# Power.net
KiCad netlist of a schematic drawn in Altium Designer
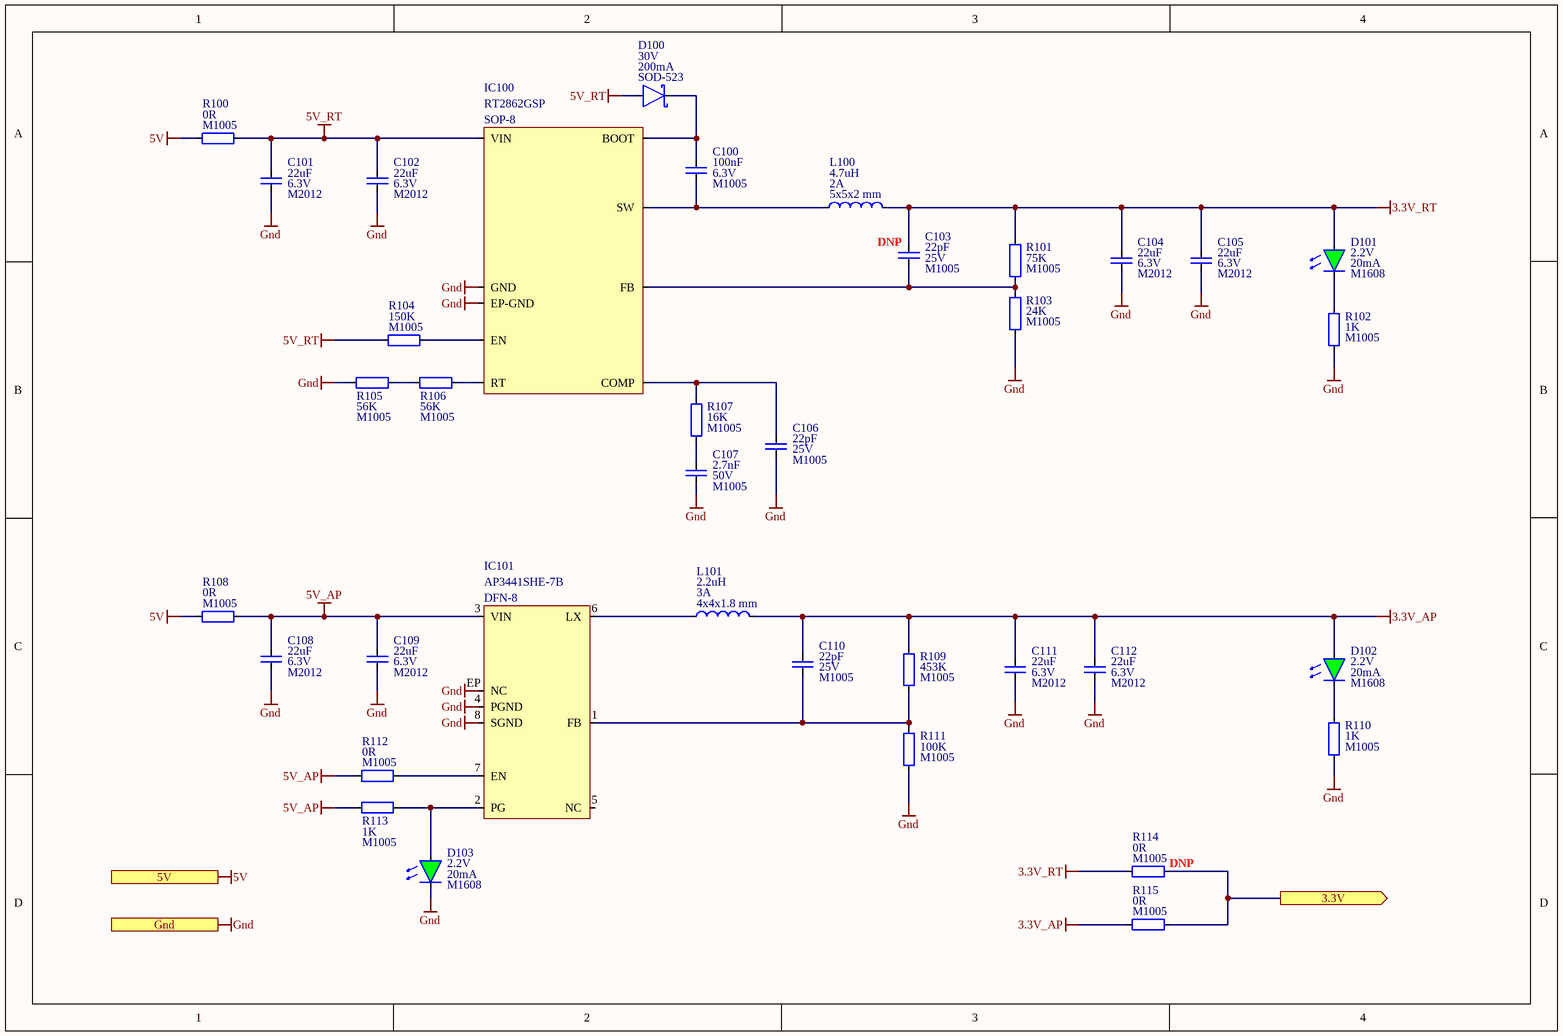
[diagram p0: Power.SchDoc]

(export (version "E")
  (design (tool "Eeschema 10.0.6"))
  (components
    (comp (ref "C100")
      (value "100nF")
      (footprint "Capacitor_Ceramic_M1005_I0402")
      (description "Cap, Cer, 100nF, 6.3V, M1005")
      (fields
        (field (name "VOLTAGE") "6.3V")
        (field (name "MANUFACTURER PART NUMBER") "04026D104KAT4A")
        (field (name "MANUFACTURER") "Kyocera")
        (field (name "PACKAGE") "M1005")
      )
      (libsource (lib "Capacitor") (part "Capacitor_Ceramic"))
    )
    (comp (ref "C101")
      (value "22uF")
      (footprint "Capacitor_Ceramic_M2012_I0805")
      (description "Cap, Cer, 22uF, 6.3V, M2012")
      (fields
        (field (name "VOLTAGE") "6.3V")
        (field (name "MANUFACTURER PART NUMBER") "GRM21BR60J226ME39K")
        (field (name "MANUFACTURER") "Murata")
        (field (name "PACKAGE") "M2012")
      )
      (libsource (lib "Capacitor") (part "Capacitor_Ceramic"))
    )
    (comp (ref "C102")
      (value "22uF")
      (footprint "Capacitor_Ceramic_M2012_I0805")
      (description "Cap, Cer, 22uF, 6.3V, M2012")
      (fields
        (field (name "VOLTAGE") "6.3V")
        (field (name "MANUFACTURER PART NUMBER") "GRM21BR60J226ME39K")
        (field (name "MANUFACTURER") "Murata")
        (field (name "PACKAGE") "M2012")
      )
      (libsource (lib "Capacitor") (part "Capacitor_Ceramic"))
    )
    (comp (ref "C103")
      (value "22pF")
      (footprint "Capacitor_Ceramic_M1005_I0402")
      (description "Cap, Cer, 22pF, 25V, M1005")
      (fields
        (field (name "VOLTAGE") "25V")
        (field (name "MANUFACTURER PART NUMBER") "0402N220J250CT")
        (field (name "MANUFACTURER") "Walsin")
        (field (name "PACKAGE") "M1005")
      )
      (libsource (lib "Capacitor") (part "Capacitor_Ceramic"))
    )
    (comp (ref "C104")
      (value "22uF")
      (footprint "Capacitor_Ceramic_M2012_I0805")
      (description "Cap, Cer, 22uF, 6.3V, M2012")
      (fields
        (field (name "VOLTAGE") "6.3V")
        (field (name "MANUFACTURER PART NUMBER") "GRM21BR60J226ME39K")
        (field (name "MANUFACTURER") "Murata")
        (field (name "PACKAGE") "M2012")
      )
      (libsource (lib "Capacitor") (part "Capacitor_Ceramic"))
    )
    (comp (ref "C105")
      (value "22uF")
      (footprint "Capacitor_Ceramic_M2012_I0805")
      (description "Cap, Cer, 22uF, 6.3V, M2012")
      (fields
        (field (name "VOLTAGE") "6.3V")
        (field (name "MANUFACTURER PART NUMBER") "GRM21BR60J226ME39K")
        (field (name "MANUFACTURER") "Murata")
        (field (name "PACKAGE") "M2012")
      )
      (libsource (lib "Capacitor") (part "Capacitor_Ceramic"))
    )
    (comp (ref "C106")
      (value "22pF")
      (footprint "Capacitor_Ceramic_M1005_I0402")
      (description "Cap, Cer, 22pF, 25V, M1005")
      (fields
        (field (name "VOLTAGE") "25V")
        (field (name "MANUFACTURER PART NUMBER") "0402N220J250CT")
        (field (name "MANUFACTURER") "Walsin")
        (field (name "PACKAGE") "M1005")
      )
      (libsource (lib "Capacitor") (part "Capacitor_Ceramic"))
    )
    (comp (ref "C107")
      (value "2.7nF")
      (footprint "Capacitor_Ceramic_M1005_I0402")
      (description "Cap, Cer, 2.7nF, 50V, M1005")
      (fields
        (field (name "VOLTAGE") "50V")
        (field (name "MANUFACTURER PART NUMBER") "CC0402KRX7R9BB272")
        (field (name "MANUFACTURER") "Walsin")
        (field (name "PACKAGE") "M1005")
      )
      (libsource (lib "Capacitor") (part "Capacitor_Ceramic"))
    )
    (comp (ref "C108")
      (value "22uF")
      (footprint "Capacitor_Ceramic_M2012_I0805")
      (description "Cap, Cer, 22uF, 6.3V, M2012")
      (fields
        (field (name "VOLTAGE") "6.3V")
        (field (name "MANUFACTURER PART NUMBER") "GRM21BR60J226ME39K")
        (field (name "MANUFACTURER") "Murata")
        (field (name "PACKAGE") "M2012")
      )
      (libsource (lib "Capacitor") (part "Capacitor_Ceramic"))
    )
    (comp (ref "C109")
      (value "22uF")
      (footprint "Capacitor_Ceramic_M2012_I0805")
      (description "Cap, Cer, 22uF, 6.3V, M2012")
      (fields
        (field (name "VOLTAGE") "6.3V")
        (field (name "MANUFACTURER PART NUMBER") "GRM21BR60J226ME39K")
        (field (name "MANUFACTURER") "Murata")
        (field (name "PACKAGE") "M2012")
      )
      (libsource (lib "Capacitor") (part "Capacitor_Ceramic"))
    )
    (comp (ref "C110")
      (value "22pF")
      (footprint "Capacitor_Ceramic_M1005_I0402")
      (description "Cap, Cer, 22pF, 25V, M1005")
      (fields
        (field (name "VOLTAGE") "25V")
        (field (name "MANUFACTURER PART NUMBER") "0402N220J250CT")
        (field (name "MANUFACTURER") "Walsin")
        (field (name "PACKAGE") "M1005")
      )
      (libsource (lib "Capacitor") (part "Capacitor_Ceramic"))
    )
    (comp (ref "C111")
      (value "22uF")
      (footprint "Capacitor_Ceramic_M2012_I0805")
      (description "Cap, Cer, 22uF, 6.3V, M2012")
      (fields
        (field (name "VOLTAGE") "6.3V")
        (field (name "MANUFACTURER PART NUMBER") "GRM21BR60J226ME39K")
        (field (name "MANUFACTURER") "Murata")
        (field (name "PACKAGE") "M2012")
      )
      (libsource (lib "Capacitor") (part "Capacitor_Ceramic"))
    )
    (comp (ref "C112")
      (value "22uF")
      (footprint "Capacitor_Ceramic_M2012_I0805")
      (description "Cap, Cer, 22uF, 6.3V, M2012")
      (fields
        (field (name "VOLTAGE") "6.3V")
        (field (name "MANUFACTURER PART NUMBER") "GRM21BR60J226ME39K")
        (field (name "MANUFACTURER") "Murata")
        (field (name "PACKAGE") "M2012")
      )
      (libsource (lib "Capacitor") (part "Capacitor_Ceramic"))
    )
    (comp (ref "D100")
      (value "Diode_Schottky")
      (footprint "Diode_SOD-523_SC-79")
      (description "Diode, Schottky, 30V, 200mA, SOD-523")
      (fields
        (field (name "MANUFACTURER PART NUMBER") "CES521,L3F")
        (field (name "MANUFACTURER") "Toshiba")
        (field (name "CURRENT") "200mA")
        (field (name "VOLTAGE") "30V")
        (field (name "PACKAGE") "SOD-523")
      )
      (libsource (lib "Diode") (part "Diode_Schottky"))
    )
    (comp (ref "D101")
      (value "Diode_Led")
      (footprint "Diode_Smd_M1608_I0603_Green-Yellow")
      (description "Diode, Led, Green-Yellow, 2.2V, 20mA, M1608")
      (fields
        (field (name "MANUFACTURER PART NUMBER") "SML-D12M1WT86")
        (field (name "MANUFACTURER") "Rohm")
        (field (name "CURRENT") "20mA")
        (field (name "VOLTAGE") "2.2V")
        (field (name "PACKAGE") "M1608")
      )
      (libsource (lib "Diode") (part "Diode_Led"))
    )
    (comp (ref "D102")
      (value "Diode_Led")
      (footprint "Diode_Smd_M1608_I0603_Green-Yellow")
      (description "Diode, Led, Green-Yellow, 2.2V, 20mA, M1608")
      (fields
        (field (name "MANUFACTURER PART NUMBER") "SML-D12M1WT86")
        (field (name "MANUFACTURER") "Rohm")
        (field (name "CURRENT") "20mA")
        (field (name "VOLTAGE") "2.2V")
        (field (name "PACKAGE") "M1608")
      )
      (libsource (lib "Diode") (part "Diode_Led"))
    )
    (comp (ref "D103")
      (value "Diode_Led")
      (footprint "Diode_Smd_M1608_I0603_Green-Yellow")
      (description "Diode, Led, Green-Yellow, 2.2V, 20mA, M1608")
      (fields
        (field (name "MANUFACTURER PART NUMBER") "SML-D12M1WT86")
        (field (name "MANUFACTURER") "Rohm")
        (field (name "CURRENT") "20mA")
        (field (name "VOLTAGE") "2.2V")
        (field (name "PACKAGE") "M1608")
      )
      (libsource (lib "Diode") (part "Diode_Led"))
    )
    (comp (ref "IC100")
      (value "Richtek, RT2862xSP")
      (footprint "Richtek, RT2862xSP, SOP-8")
      (description "IC, Power, Buck, SOP-8")
      (fields
        (field (name "MANUFACTURER") "Richtek")
        (field (name "MANUFACTURER PART NUMBER") "RT2862GSP")
        (field (name "PACKAGE") "SOP-8")
      )
      (libsource (lib "IC - Power - DC-DC") (part "Richtek, RT2862xSP"))
    )
    (comp (ref "IC101")
      (value "Diodes, AP3441")
      (footprint "DFN-8, 2mm x 2mm, 0.5mm")
      (description "IC, Power, Buck, DFN-8, 2x2")
      (fields
        (field (name "MANUFACTURER") "Richtek")
        (field (name "MANUFACTURER PART NUMBER") "AP3441SHE-7B")
        (field (name "PACKAGE") "DFN-8")
      )
      (libsource (lib "IC - Power - DC-DC") (part "Diodes, AP3441"))
    )
    (comp (ref "L100")
      (value "4.7uH")
      (footprint "Taiyo Yuden - Power Inductor, 5050WK")
      (description "Inductor, Power, 4.7uH, 2A, 5x5x2mm")
      (fields
        (field (name "MANUFACTURER PART NUMBER") "NRS5020T4R7MMGJ")
        (field (name "MANUFACTURER") "Taiyo Yuden")
        (field (name "SATURATION CURRENT") "2A")
        (field (name "PACKAGE") "5x5x2 mm")
      )
      (libsource (lib "Inductor") (part "Inductor"))
    )
    (comp (ref "L101")
      (value "2.2uH")
      (footprint "Taiyo Yuden - Power Inductor, 4040TK")
      (description "Inductor, Power, 2.2uH, 3A, 4x4x1.8mm")
      (fields
        (field (name "MANUFACTURER PART NUMBER") "NRS4018T2R2MDGJ")
        (field (name "MANUFACTURER") "Taiyo Yuden")
        (field (name "SATURATION CURRENT") "3A")
        (field (name "PACKAGE") "4x4x1.8 mm")
      )
      (libsource (lib "Inductor") (part "Inductor"))
    )
    (comp (ref "R100")
      (value "0R")
      (footprint "Resistor_Smd_M1005_I0402")
      (description "Res, 0R, M1005")
      (fields
        (field (name "MANUFACTURER") "Yageo")
        (field (name "MANUFACTURER PART NUMBER") "RC0402FR-070RL")
        (field (name "PACKAGE") "M1005")
      )
      (libsource (lib "Resistor") (part "Resistor"))
    )
    (comp (ref "R101")
      (value "75K")
      (footprint "Resistor_Smd_M1005_I0402")
      (description "Res, 75K, 1%, M1005")
      (fields
        (field (name "TOLERANCE") "1%")
        (field (name "MANUFACTURER") "Yageo")
        (field (name "PACKAGE") "M1005")
      )
      (libsource (lib "Resistor") (part "Resistor"))
    )
    (comp (ref "R102")
      (value "1K")
      (footprint "Resistor_Smd_M1005_I0402")
      (description "Res, 1K, 1%, M1005")
      (fields
        (field (name "TOLERANCE") "1%")
        (field (name "MANUFACTURER") "Yageo")
        (field (name "PACKAGE") "M1005")
      )
      (libsource (lib "Resistor") (part "Resistor"))
    )
    (comp (ref "R103")
      (value "24K")
      (footprint "Resistor_Smd_M1005_I0402")
      (description "Res, 24K, 1%, M1005")
      (fields
        (field (name "TOLERANCE") "1%")
        (field (name "MANUFACTURER") "Yageo")
        (field (name "PACKAGE") "M1005")
      )
      (libsource (lib "Resistor") (part "Resistor"))
    )
    (comp (ref "R104")
      (value "150K")
      (footprint "Resistor_Smd_M1005_I0402")
      (description "Res, 150K, 1%, M1005")
      (fields
        (field (name "TOLERANCE") "1%")
        (field (name "MANUFACTURER") "Yageo")
        (field (name "PACKAGE") "M1005")
      )
      (libsource (lib "Resistor") (part "Resistor"))
    )
    (comp (ref "R105")
      (value "56K")
      (footprint "Resistor_Smd_M1005_I0402")
      (description "Res, 56K, 1%, M1005")
      (fields
        (field (name "TOLERANCE") "1%")
        (field (name "MANUFACTURER") "Yageo")
        (field (name "PACKAGE") "M1005")
      )
      (libsource (lib "Resistor") (part "Resistor"))
    )
    (comp (ref "R106")
      (value "56K")
      (footprint "Resistor_Smd_M1005_I0402")
      (description "Res, 56K, 1%, M1005")
      (fields
        (field (name "TOLERANCE") "1%")
        (field (name "MANUFACTURER") "Yageo")
        (field (name "PACKAGE") "M1005")
      )
      (libsource (lib "Resistor") (part "Resistor"))
    )
    (comp (ref "R107")
      (value "16K")
      (footprint "Resistor_Smd_M1005_I0402")
      (description "Res, 16K, 1%, M1005")
      (fields
        (field (name "TOLERANCE") "1%")
        (field (name "MANUFACTURER") "Yageo")
        (field (name "PACKAGE") "M1005")
      )
      (libsource (lib "Resistor") (part "Resistor"))
    )
    (comp (ref "R108")
      (value "0R")
      (footprint "Resistor_Smd_M1005_I0402")
      (description "Res, 0R, M1005")
      (fields
        (field (name "MANUFACTURER") "Yageo")
        (field (name "MANUFACTURER PART NUMBER") "RC0402FR-070RL")
        (field (name "PACKAGE") "M1005")
      )
      (libsource (lib "Resistor") (part "Resistor"))
    )
    (comp (ref "R109")
      (value "453K")
      (footprint "Resistor_Smd_M1005_I0402")
      (description "Res, 453K, 1%, M1005")
      (fields
        (field (name "TOLERANCE") "1%")
        (field (name "MANUFACTURER") "Yageo")
        (field (name "PACKAGE") "M1005")
      )
      (libsource (lib "Resistor") (part "Resistor"))
    )
    (comp (ref "R110")
      (value "1K")
      (footprint "Resistor_Smd_M1005_I0402")
      (description "Res, 1K, 1%, M1005")
      (fields
        (field (name "TOLERANCE") "1%")
        (field (name "MANUFACTURER") "Yageo")
        (field (name "PACKAGE") "M1005")
      )
      (libsource (lib "Resistor") (part "Resistor"))
    )
    (comp (ref "R111")
      (value "100K")
      (footprint "Resistor_Smd_M1005_I0402")
      (description "Res, 100K, 1%, M1005")
      (fields
        (field (name "TOLERANCE") "1%")
        (field (name "MANUFACTURER") "Yageo")
        (field (name "PACKAGE") "M1005")
      )
      (libsource (lib "Resistor") (part "Resistor"))
    )
    (comp (ref "R112")
      (value "0R")
      (footprint "Resistor_Smd_M1005_I0402")
      (description "Res, 0R, M1005")
      (fields
        (field (name "MANUFACTURER") "Yageo")
        (field (name "MANUFACTURER PART NUMBER") "RC0402FR-070RL")
        (field (name "PACKAGE") "M1005")
      )
      (libsource (lib "Resistor") (part "Resistor"))
    )
    (comp (ref "R113")
      (value "1K")
      (footprint "Resistor_Smd_M1005_I0402")
      (description "Res, 1K, 1%, M1005")
      (fields
        (field (name "TOLERANCE") "1%")
        (field (name "MANUFACTURER") "Yageo")
        (field (name "PACKAGE") "M1005")
      )
      (libsource (lib "Resistor") (part "Resistor"))
    )
    (comp (ref "R114")
      (value "0R")
      (footprint "Resistor_Smd_M1005_I0402")
      (description "Res, 0R, M1005")
      (fields
        (field (name "MANUFACTURER") "Yageo")
        (field (name "MANUFACTURER PART NUMBER") "RC0402FR-070RL")
        (field (name "PACKAGE") "M1005")
      )
      (libsource (lib "Resistor") (part "Resistor"))
    )
    (comp (ref "R115")
      (value "0R")
      (footprint "Resistor_Smd_M1005_I0402")
      (description "Res, 0R, M1005")
      (fields
        (field (name "MANUFACTURER") "Yageo")
        (field (name "MANUFACTURER PART NUMBER") "RC0402FR-070RL")
        (field (name "PACKAGE") "M1005")
      )
      (libsource (lib "Resistor") (part "Resistor"))
    )
  )
  (nets
    (net (code "1") (name "/3.3V") (class "Default")
      (node (ref "R114") (pin "2") (pinfunction "2_2") (pintype "passive"))
      (node (ref "R115") (pin "2") (pinfunction "2_2") (pintype "passive"))
    )
    (net (code "2") (name "3.3V_AP") (class "Default")
      (node (ref "C110") (pin "1") (pinfunction "1_1") (pintype "passive"))
      (node (ref "C111") (pin "1") (pinfunction "1_1") (pintype "passive"))
      (node (ref "C112") (pin "1") (pinfunction "1_1") (pintype "passive"))
      (node (ref "D102") (pin "A") (pinfunction "A_A") (pintype "passive"))
      (node (ref "L101") (pin "2") (pinfunction "2_2") (pintype "passive"))
      (node (ref "R109") (pin "1") (pinfunction "1_1") (pintype "passive"))
      (node (ref "R115") (pin "1") (pinfunction "1_1") (pintype "passive"))
    )
    (net (code "3") (name "3.3V_RT") (class "Default")
      (node (ref "C103") (pin "1") (pinfunction "1_1") (pintype "passive"))
      (node (ref "C104") (pin "1") (pinfunction "1_1") (pintype "passive"))
      (node (ref "C105") (pin "1") (pinfunction "1_1") (pintype "passive"))
      (node (ref "D101") (pin "A") (pinfunction "A_A") (pintype "passive"))
      (node (ref "L100") (pin "2") (pinfunction "2_2") (pintype "passive"))
      (node (ref "R101") (pin "1") (pinfunction "1_1") (pintype "passive"))
      (node (ref "R114") (pin "1") (pinfunction "1_1") (pintype "passive"))
    )
    (net (code "4") (name "5V") (class "Default")
      (node (ref "R100") (pin "1") (pinfunction "1_1") (pintype "passive"))
      (node (ref "R108") (pin "1") (pinfunction "1_1") (pintype "passive"))
    )
    (net (code "5") (name "5V_AP") (class "Default")
      (node (ref "C108") (pin "1") (pinfunction "1_1") (pintype "passive"))
      (node (ref "C109") (pin "1") (pinfunction "1_1") (pintype "passive"))
      (node (ref "IC101") (pin "3") (pinfunction "VIN_3") (pintype "passive"))
      (node (ref "R108") (pin "2") (pinfunction "2_2") (pintype "passive"))
      (node (ref "R112") (pin "1") (pinfunction "1_1") (pintype "passive"))
      (node (ref "R113") (pin "1") (pinfunction "1_1") (pintype "passive"))
    )
    (net (code "6") (name "5V_RT") (class "Default")
      (node (ref "C101") (pin "1") (pinfunction "1_1") (pintype "passive"))
      (node (ref "C102") (pin "1") (pinfunction "1_1") (pintype "passive"))
      (node (ref "D100") (pin "A") (pinfunction "A_A") (pintype "passive"))
      (node (ref "IC100") (pin "8-VIN") (pinfunction "VIN_8-VIN") (pintype "passive"))
      (node (ref "R100") (pin "2") (pinfunction "2_2") (pintype "passive"))
      (node (ref "R104") (pin "1") (pinfunction "1_1") (pintype "passive"))
    )
    (net (code "7") (name "Gnd") (class "Default")
      (node (ref "C101") (pin "2") (pinfunction "2_2") (pintype "passive"))
      (node (ref "C102") (pin "2") (pinfunction "2_2") (pintype "passive"))
      (node (ref "C104") (pin "2") (pinfunction "2_2") (pintype "passive"))
      (node (ref "C105") (pin "2") (pinfunction "2_2") (pintype "passive"))
      (node (ref "C106") (pin "2") (pinfunction "2_2") (pintype "passive"))
      (node (ref "C107") (pin "2") (pinfunction "2_2") (pintype "passive"))
      (node (ref "C108") (pin "2") (pinfunction "2_2") (pintype "passive"))
      (node (ref "C109") (pin "2") (pinfunction "2_2") (pintype "passive"))
      (node (ref "C111") (pin "2") (pinfunction "2_2") (pintype "passive"))
      (node (ref "C112") (pin "2") (pinfunction "2_2") (pintype "passive"))
      (node (ref "D103") (pin "C") (pinfunction "C_C") (pintype "passive"))
      (node (ref "IC100") (pin "4-GND") (pinfunction "GND_4-GND") (pintype "passive"))
      (node (ref "IC100") (pin "EP-GND") (pinfunction "EP-GND_EP-GND") (pintype "passive"))
      (node (ref "IC101") (pin "4") (pinfunction "PGND_4") (pintype "passive"))
      (node (ref "IC101") (pin "8") (pinfunction "SGND_8") (pintype "passive"))
      (node (ref "IC101") (pin "EP") (pinfunction "NC_EP") (pintype "passive"))
      (node (ref "R102") (pin "2") (pinfunction "2_2") (pintype "passive"))
      (node (ref "R103") (pin "2") (pinfunction "2_2") (pintype "passive"))
      (node (ref "R105") (pin "1") (pinfunction "1_1") (pintype "passive"))
      (node (ref "R110") (pin "2") (pinfunction "2_2") (pintype "passive"))
      (node (ref "R111") (pin "2") (pinfunction "2_2") (pintype "passive"))
    )
    (net (code "8") (name "Net-(C107-Pad1)") (class "Default")
      (node (ref "C107") (pin "1") (pinfunction "1_1") (pintype "passive"))
      (node (ref "R107") (pin "2") (pinfunction "2_2") (pintype "passive"))
    )
    (net (code "9") (name "Net-(D101-PadC)") (class "Default")
      (node (ref "D101") (pin "C") (pinfunction "C_C") (pintype "passive"))
      (node (ref "R102") (pin "1") (pinfunction "1_1") (pintype "passive"))
    )
    (net (code "10") (name "Net-(D102-PadC)") (class "Default")
      (node (ref "D102") (pin "C") (pinfunction "C_C") (pintype "passive"))
      (node (ref "R110") (pin "1") (pinfunction "1_1") (pintype "passive"))
    )
    (net (code "11") (name "Net-(IC100-BOOT)") (class "Default")
      (node (ref "C100") (pin "1") (pinfunction "1_1") (pintype "passive"))
      (node (ref "D100") (pin "C") (pinfunction "C_C") (pintype "passive"))
      (node (ref "IC100") (pin "2-BOOT") (pinfunction "BOOT_2-BOOT") (pintype "passive"))
    )
    (net (code "12") (name "Net-(IC100-COMP)") (class "Default")
      (node (ref "C106") (pin "1") (pinfunction "1_1") (pintype "passive"))
      (node (ref "IC100") (pin "6-COMP") (pinfunction "COMP_6-COMP") (pintype "passive"))
      (node (ref "R107") (pin "1") (pinfunction "1_1") (pintype "passive"))
    )
    (net (code "13") (name "Net-(IC100-EN)") (class "Default")
      (node (ref "IC100") (pin "3-EN") (pinfunction "EN_3-EN") (pintype "passive"))
      (node (ref "R104") (pin "2") (pinfunction "2_2") (pintype "passive"))
    )
    (net (code "14") (name "Net-(IC100-FB)") (class "Default")
      (node (ref "C103") (pin "2") (pinfunction "2_2") (pintype "passive"))
      (node (ref "IC100") (pin "5-FB") (pinfunction "FB_5-FB") (pintype "passive"))
      (node (ref "R101") (pin "2") (pinfunction "2_2") (pintype "passive"))
      (node (ref "R103") (pin "1") (pinfunction "1_1") (pintype "passive"))
    )
    (net (code "15") (name "Net-(IC100-RT)") (class "Default")
      (node (ref "IC100") (pin "7-RT") (pinfunction "RT_7-RT") (pintype "passive"))
      (node (ref "R106") (pin "2") (pinfunction "2_2") (pintype "passive"))
    )
    (net (code "16") (name "Net-(IC100-SW)") (class "Default")
      (node (ref "C100") (pin "2") (pinfunction "2_2") (pintype "passive"))
      (node (ref "IC100") (pin "1-SW") (pinfunction "SW_1-SW") (pintype "passive"))
      (node (ref "L100") (pin "1") (pinfunction "1_1") (pintype "passive"))
    )
    (net (code "17") (name "Net-(IC101-EN)") (class "Default")
      (node (ref "IC101") (pin "7") (pinfunction "EN_7") (pintype "passive"))
      (node (ref "R112") (pin "2") (pinfunction "2_2") (pintype "passive"))
    )
    (net (code "18") (name "Net-(IC101-FB)") (class "Default")
      (node (ref "C110") (pin "2") (pinfunction "2_2") (pintype "passive"))
      (node (ref "IC101") (pin "1") (pinfunction "FB_1") (pintype "passive"))
      (node (ref "R109") (pin "2") (pinfunction "2_2") (pintype "passive"))
      (node (ref "R111") (pin "1") (pinfunction "1_1") (pintype "passive"))
    )
    (net (code "19") (name "Net-(IC101-LX)") (class "Default")
      (node (ref "IC101") (pin "6") (pinfunction "LX_6") (pintype "passive"))
      (node (ref "L101") (pin "1") (pinfunction "1_1") (pintype "passive"))
    )
    (net (code "20") (name "Net-(IC101-PG)") (class "Default")
      (node (ref "D103") (pin "A") (pinfunction "A_A") (pintype "passive"))
      (node (ref "IC101") (pin "2") (pinfunction "PG_2") (pintype "passive"))
      (node (ref "R113") (pin "2") (pinfunction "2_2") (pintype "passive"))
    )
    (net (code "21") (name "Net-(R105-Pad2)") (class "Default")
      (node (ref "R105") (pin "2") (pinfunction "2_2") (pintype "passive"))
      (node (ref "R106") (pin "1") (pinfunction "1_1") (pintype "passive"))
    )
    (net (code "22") (name "unconnected-(IC101-NC-Pad5)") (class "Default")
      (node (ref "IC101") (pin "5") (pinfunction "NC_5") (pintype "passive"))
    )
  )
)
